# 2CH_Edgemount_POT.net
KiCad netlist of a schematic drawn in EAGLE
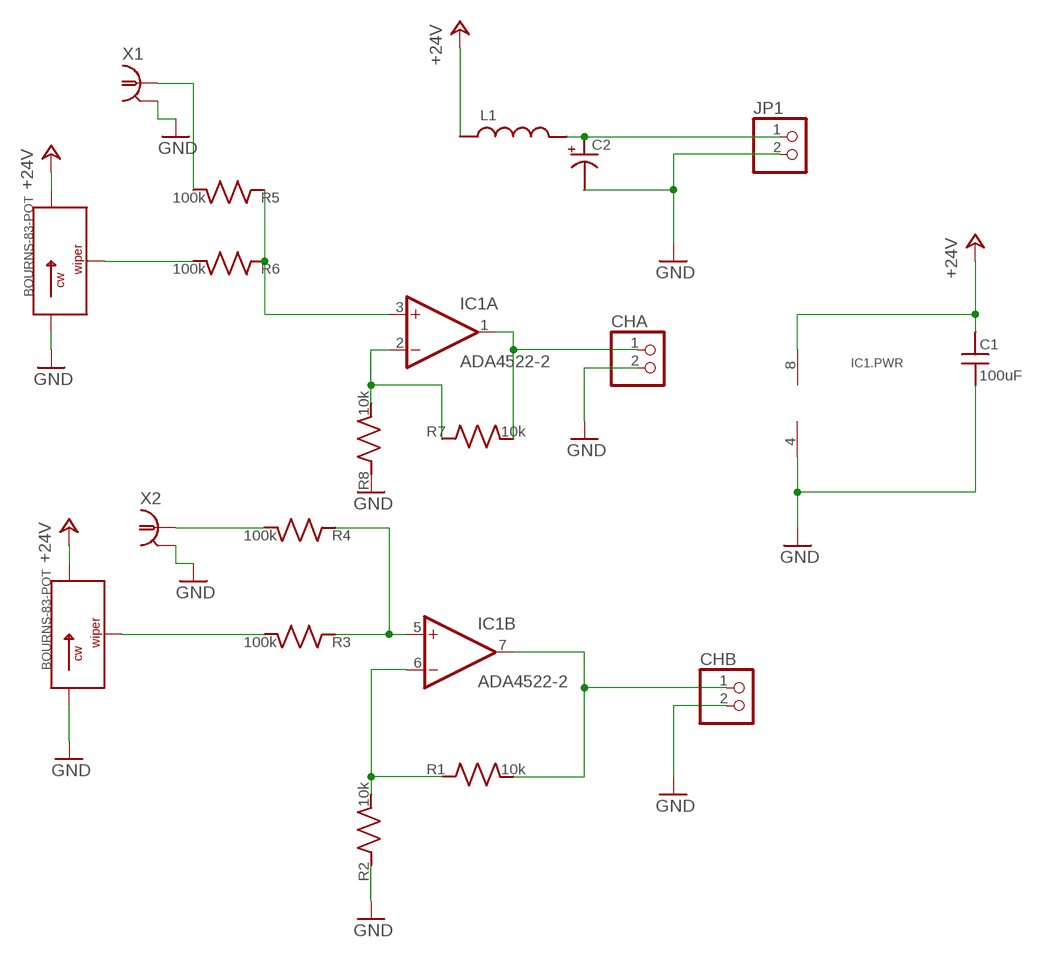
[diagram p0: schematic, sheet 1]

(export (version "E")
  (design (tool "Eeschema 10.0.6"))
  (components
    (comp (ref "C1")
      (value "100uF")
      (footprint "eagle-import:C_MLCC_0603")
      (libsource (lib "eagle-import") (part "C_MLCC_SMDCMLCC_0603"))
    )
    (comp (ref "C2")
      (value "C_POL_SMDF")
      (footprint "eagle-import:PANASONIC_F")
      (libsource (lib "eagle-import") (part "C_POL_SMDF"))
    )
    (comp (ref "CHA")
      (value "PINHD-1X2")
      (footprint "eagle-import:1X02")
      (libsource (lib "eagle-import") (part "PINHD-1X2"))
    )
    (comp (ref "CHB")
      (value "PINHD-1X2")
      (footprint "eagle-import:1X02")
      (libsource (lib "eagle-import") (part "PINHD-1X2"))
    )
    (comp (ref "IC1")
      (value "ADA4522-2")
      (footprint "eagle-import:SO08")
      (libsource (lib "eagle-import") (part "ADA4522-2"))
    )
    (comp (ref "JP1")
      (value "PINHD-1X2")
      (footprint "eagle-import:1X02")
      (libsource (lib "eagle-import") (part "PINHD-1X2"))
    )
    (comp (ref "L1")
      (value "L_FERRITE_SMDLFERRITE_0805")
      (footprint "eagle-import:R_0805")
      (libsource (lib "eagle-import") (part "L_FERRITE_SMDLFERRITE_0805"))
    )
    (comp (ref "R1")
      (value "10k")
      (footprint "eagle-import:R_1206")
      (libsource (lib "eagle-import") (part "R_SMDR1206"))
    )
    (comp (ref "R2")
      (value "10k")
      (footprint "eagle-import:R_1206")
      (libsource (lib "eagle-import") (part "R_SMDR1206"))
    )
    (comp (ref "R3")
      (value "100k")
      (footprint "eagle-import:R_1206")
      (libsource (lib "eagle-import") (part "R_SMDR1206"))
    )
    (comp (ref "R4")
      (value "100k")
      (footprint "eagle-import:R_1206")
      (libsource (lib "eagle-import") (part "R_SMDR1206"))
    )
    (comp (ref "R5")
      (value "100k")
      (footprint "eagle-import:R_1206")
      (libsource (lib "eagle-import") (part "R_SMDR1206"))
    )
    (comp (ref "R6")
      (value "100k")
      (footprint "eagle-import:R_1206")
      (libsource (lib "eagle-import") (part "R_SMDR1206"))
    )
    (comp (ref "R7")
      (value "10k")
      (footprint "eagle-import:R_1206")
      (libsource (lib "eagle-import") (part "R_SMDR1206"))
    )
    (comp (ref "R8")
      (value "10k")
      (footprint "eagle-import:R_1206")
      (libsource (lib "eagle-import") (part "R_SMDR1206"))
    )
    (comp (ref "R9")
      (value "BOURNS-83-POT")
      (footprint "eagle-import:BOURNS83")
      (libsource (lib "eagle-import") (part "BOURNS-83-POT"))
    )
    (comp (ref "R10")
      (value "BOURNS-83-POT")
      (footprint "eagle-import:BOURNS83")
      (libsource (lib "eagle-import") (part "BOURNS-83-POT"))
    )
    (comp (ref "X1")
      (value "BNC-H")
      (footprint "eagle-import:BNC90")
      (libsource (lib "eagle-import") (part "BNC-H"))
    )
    (comp (ref "X2")
      (value "BNC-H")
      (footprint "eagle-import:BNC90")
      (libsource (lib "eagle-import") (part "BNC-H"))
    )
  )
  (nets
    (net (code "1") (name "+24V") (class "Default")
      (node (ref "C1") (pin "P$1") (pinfunction "1_P$1") (pintype "passive"))
      (node (ref "IC1") (pin "8") (pinfunction "V+_8") (pintype "power_in"))
      (node (ref "L1") (pin "P$1") (pinfunction "1_P$1") (pintype "passive"))
      (node (ref "R10") (pin "P$3") (pinfunction "P$3_P$3") (pintype "bidirectional"))
      (node (ref "R9") (pin "P$3") (pinfunction "P$3_P$3") (pintype "bidirectional"))
    )
    (net (code "2") (name "GND") (class "Default")
      (node (ref "C1") (pin "P$2") (pinfunction "2_P$2") (pintype "passive"))
      (node (ref "C2") (pin "-") (pinfunction "-_-") (pintype "passive"))
      (node (ref "CHA") (pin "2") (pinfunction "2_2") (pintype "passive"))
      (node (ref "CHB") (pin "2") (pinfunction "2_2") (pintype "passive"))
      (node (ref "IC1") (pin "4") (pinfunction "V-_4") (pintype "power_in"))
      (node (ref "JP1") (pin "2") (pinfunction "2_2") (pintype "passive"))
      (node (ref "R10") (pin "P$1") (pinfunction "P$1_P$1") (pintype "bidirectional"))
      (node (ref "R2") (pin "P$1") (pinfunction "1_P$1") (pintype "passive"))
      (node (ref "R8") (pin "P$1") (pinfunction "1_P$1") (pintype "passive"))
      (node (ref "R9") (pin "P$1") (pinfunction "P$1_P$1") (pintype "bidirectional"))
      (node (ref "X1") (pin "2") (pinfunction "2_2") (pintype "passive"))
      (node (ref "X2") (pin "2") (pinfunction "2_2") (pintype "passive"))
    )
    (net (code "3") (name "Net-(IC1B-+IN)") (class "Default")
      (node (ref "IC1") (pin "3") (pinfunction "+IN_3") (pintype "input"))
      (node (ref "R5") (pin "P$1") (pinfunction "1_P$1") (pintype "passive"))
      (node (ref "R6") (pin "P$1") (pinfunction "1_P$1") (pintype "passive"))
    )
    (net (code "4") (name "Net-(IC1B--IN)") (class "Default")
      (node (ref "IC1") (pin "2") (pinfunction "-IN_2") (pintype "input"))
      (node (ref "R7") (pin "P$1") (pinfunction "1_P$1") (pintype "passive"))
      (node (ref "R8") (pin "P$2") (pinfunction "2_P$2") (pintype "passive"))
    )
    (net (code "5") (name "Net-(IC1B-OUT)") (class "Default")
      (node (ref "CHA") (pin "1") (pinfunction "1_1") (pintype "passive"))
      (node (ref "IC1") (pin "1") (pinfunction "OUT_1") (pintype "output"))
      (node (ref "R7") (pin "P$2") (pinfunction "2_P$2") (pintype "passive"))
    )
    (net (code "6") (name "Net-(IC1C-+IN)") (class "Default")
      (node (ref "IC1") (pin "5") (pinfunction "+IN_5") (pintype "input"))
      (node (ref "R3") (pin "P$1") (pinfunction "1_P$1") (pintype "passive"))
      (node (ref "R4") (pin "P$1") (pinfunction "1_P$1") (pintype "passive"))
    )
    (net (code "7") (name "Net-(IC1C--IN)") (class "Default")
      (node (ref "IC1") (pin "6") (pinfunction "-IN_6") (pintype "input"))
      (node (ref "R1") (pin "P$1") (pinfunction "1_P$1") (pintype "passive"))
      (node (ref "R2") (pin "P$2") (pinfunction "2_P$2") (pintype "passive"))
    )
    (net (code "8") (name "Net-(IC1C-OUT)") (class "Default")
      (node (ref "CHB") (pin "1") (pinfunction "1_1") (pintype "passive"))
      (node (ref "IC1") (pin "7") (pinfunction "OUT_7") (pintype "output"))
      (node (ref "R1") (pin "P$2") (pinfunction "2_P$2") (pintype "passive"))
    )
    (net (code "9") (name "Net-(L1-2)") (class "Default")
      (node (ref "C2") (pin "+") (pinfunction "+_+") (pintype "passive"))
      (node (ref "JP1") (pin "1") (pinfunction "1_1") (pintype "passive"))
      (node (ref "L1") (pin "P$2") (pinfunction "2_P$2") (pintype "passive"))
    )
    (net (code "10") (name "Net-(R3-2)") (class "Default")
      (node (ref "R10") (pin "P$2") (pinfunction "P$2_P$2") (pintype "bidirectional"))
      (node (ref "R3") (pin "P$2") (pinfunction "2_P$2") (pintype "passive"))
    )
    (net (code "11") (name "Net-(R4-2)") (class "Default")
      (node (ref "R4") (pin "P$2") (pinfunction "2_P$2") (pintype "passive"))
      (node (ref "X2") (pin "1") (pinfunction "1_1") (pintype "passive"))
    )
    (net (code "12") (name "Net-(R5-2)") (class "Default")
      (node (ref "R5") (pin "P$2") (pinfunction "2_P$2") (pintype "passive"))
      (node (ref "X1") (pin "1") (pinfunction "1_1") (pintype "passive"))
    )
    (net (code "13") (name "Net-(R6-2)") (class "Default")
      (node (ref "R6") (pin "P$2") (pinfunction "2_P$2") (pintype "passive"))
      (node (ref "R9") (pin "P$2") (pinfunction "P$2_P$2") (pintype "bidirectional"))
    )
  )
)
